# sensors.net
KiCad netlist of a schematic drawn in Altium Designer
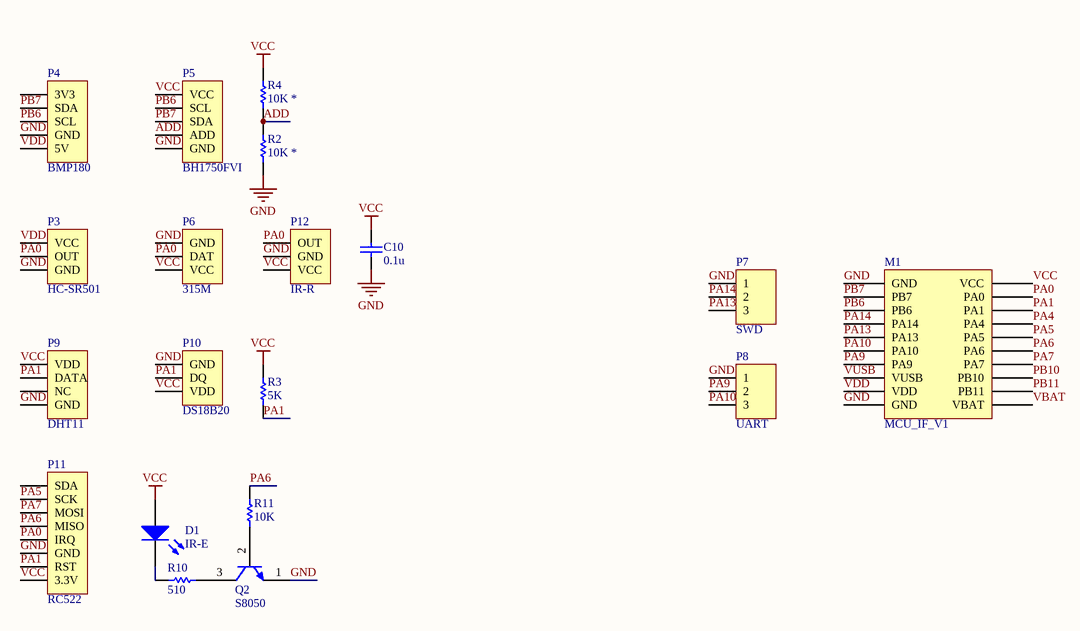
[diagram p0: sensors.SchDoc]

(export (version "E")
  (design (tool "Eeschema 10.0.6"))
  (components
    (comp (ref "C10")
      (value "0.1u")
      (footprint "C-1608[0603]")
      (description "Capacitor (Semiconductor SIM Model)")
      (fields (field (name "Comment") "Cap Semi") (field (name "PUBLISHER") "Altium Limited"))
      (libsource (lib "Miscellaneous Devices") (part "Cap Semi"))
    )
    (comp (ref "D1")
      (value "IR-E")
      (footprint "PIN2")
      (description "Typical INFRARED GaAs LED")
      (fields (field (name "PUBLISHER") "Altium Limited"))
      (libsource (lib "Miscellaneous Devices") (part "LED0"))
    )
    (comp (ref "M1")
      (value "MCU_IF_V1")
      (footprint "MCU_IF_V1")
      (libsource (lib "MCU_IF") (part "MCU_IF_V1"))
    )
    (comp (ref "P3")
      (value "HC-SR501")
      (footprint "HDR1X3")
      (description "Header, 3-Pin")
      (fields (field (name "PUBLISHER") "Altium Limited"))
      (libsource (lib "sensor_ifce") (part "HC-SR501"))
    )
    (comp (ref "P4")
      (value "BMP180")
      (footprint "HDR1X5")
      (description "Header, 5-Pin")
      (fields (field (name "PUBLISHER") "Altium Limited"))
      (libsource (lib "sensor_ifce") (part "BMP180"))
    )
    (comp (ref "P5")
      (value "BH1750FVI")
      (footprint "HDR1X5")
      (fields (field (name "PUBLISHER") "Altium Limited"))
      (libsource (lib "sensor_ifce") (part "BH1750FVI"))
    )
    (comp (ref "P6")
      (value "315M")
      (footprint "HDR1X3")
      (description "Header, 3-Pin")
      (fields (field (name "PUBLISHER") "Altium Limited"))
      (libsource (lib "sensor_ifce") (part "315M"))
    )
    (comp (ref "P7")
      (value "SWD")
      (footprint "HDR1X3")
      (description "Header, 3-Pin")
      (fields (field (name "PUBLISHER") "Altium Limited"))
      (libsource (lib "Miscellaneous Connectors") (part "Header 3"))
    )
    (comp (ref "P8")
      (value "UART")
      (footprint "HDR1X3")
      (description "Header, 3-Pin")
      (fields (field (name "PUBLISHER") "Altium Limited"))
      (libsource (lib "Miscellaneous Connectors") (part "Header 3"))
    )
    (comp (ref "P9")
      (value "DHT11")
      (footprint "HDR1X4")
      (description "Header, 4-Pin")
      (fields (field (name "PUBLISHER") "Altium Limited"))
      (libsource (lib "sensor_ifce") (part "DHT11"))
    )
    (comp (ref "P10")
      (value "DS18B20")
      (footprint "HDR1X3")
      (description "Header, 3-Pin")
      (fields (field (name "PUBLISHER") "Altium Limited"))
      (libsource (lib "sensor_ifce") (part "DS18B20"))
    )
    (comp (ref "P11")
      (value "RC522")
      (footprint "HDR1X8")
      (description "Header, 8-Pin")
      (fields (field (name "PUBLISHER") "Altium Limited"))
      (libsource (lib "sensor_ifce") (part "RC522"))
    )
    (comp (ref "P12")
      (value "IR-R")
      (footprint "HDR1X3")
      (description "Header, 3-Pin")
      (fields (field (name "PUBLISHER") "Altium Limited"))
      (libsource (lib "sensor_ifce") (part "IR"))
    )
    (comp (ref "Q2")
      (value "S8050")
      (footprint "SOT23B")
      (description "NPN General Purpose Amplifier")
      (fields (field (name "PUBLISHER") "Altium Limited"))
      (libsource (lib "Miscellaneous Devices") (part "2N3904"))
    )
    (comp (ref "R2")
      (value "10K *")
      (footprint "R-1608[0603]")
      (description "Semiconductor Resistor")
      (fields (field (name "Comment") "Res Semi") (field (name "PUBLISHER") "Altium Limited"))
      (libsource (lib "Miscellaneous Devices") (part "Res Semi"))
    )
    (comp (ref "R3")
      (value "5K")
      (footprint "R-1608[0603]")
      (description "Semiconductor Resistor")
      (fields (field (name "Comment") "Res Semi") (field (name "PUBLISHER") "Altium Limited"))
      (libsource (lib "Miscellaneous Devices") (part "Res Semi"))
    )
    (comp (ref "R4")
      (value "10K *")
      (footprint "R-1608[0603]")
      (description "Semiconductor Resistor")
      (fields (field (name "Comment") "Res Semi") (field (name "PUBLISHER") "Altium Limited"))
      (libsource (lib "Miscellaneous Devices") (part "Res Semi"))
    )
    (comp (ref "R10")
      (value "510")
      (footprint "R-1608[0603]")
      (description "Semiconductor Resistor")
      (fields (field (name "Comment") "Res Semi") (field (name "PUBLISHER") "Altium Limited"))
      (libsource (lib "Miscellaneous Devices") (part "Res Semi"))
    )
    (comp (ref "R11")
      (value "10K")
      (footprint "R-1608[0603]")
      (description "Semiconductor Resistor")
      (fields (field (name "Comment") "Res Semi") (field (name "PUBLISHER") "Altium Limited"))
      (libsource (lib "Miscellaneous Devices") (part "Res Semi"))
    )
  )
  (nets
    (net (code "1") (name "/ADD") (class "Default")
      (node (ref "P5") (pin "4") (pinfunction "ADD_4") (pintype "passive"))
      (node (ref "R2") (pin "1") (pinfunction "1_1") (pintype "passive"))
      (node (ref "R4") (pin "2") (pinfunction "2_2") (pintype "passive"))
    )
    (net (code "2") (name "/PA0") (class "Default")
      (node (ref "M1") (pin "19") (pinfunction "PA0_19") (pintype "passive"))
      (node (ref "P11") (pin "5") (pinfunction "IRQ_5") (pintype "passive"))
      (node (ref "P12") (pin "1") (pinfunction "OUT_1") (pintype "passive"))
      (node (ref "P3") (pin "2") (pinfunction "OUT_2") (pintype "passive"))
      (node (ref "P6") (pin "2") (pinfunction "DAT_2") (pintype "passive"))
    )
    (net (code "3") (name "/PA1") (class "Default")
      (node (ref "M1") (pin "18") (pinfunction "PA1_18") (pintype "passive"))
      (node (ref "P10") (pin "2") (pinfunction "DQ_2") (pintype "passive"))
      (node (ref "P11") (pin "7") (pinfunction "RST_7") (pintype "passive"))
      (node (ref "P9") (pin "2") (pinfunction "DATA_2") (pintype "passive"))
      (node (ref "R3") (pin "2") (pinfunction "2_2") (pintype "passive"))
    )
    (net (code "4") (name "/PA4") (class "Default")
      (node (ref "M1") (pin "17") (pinfunction "PA4_17") (pintype "passive"))
    )
    (net (code "5") (name "/PA5") (class "Default")
      (node (ref "M1") (pin "16") (pinfunction "PA5_16") (pintype "passive"))
      (node (ref "P11") (pin "2") (pinfunction "SCK_2") (pintype "passive"))
    )
    (net (code "6") (name "/PA6") (class "Default")
      (node (ref "M1") (pin "15") (pinfunction "PA6_15") (pintype "passive"))
      (node (ref "P11") (pin "4") (pinfunction "MISO_4") (pintype "passive"))
      (node (ref "R11") (pin "2") (pinfunction "2_2") (pintype "passive"))
    )
    (net (code "7") (name "/PA7") (class "Default")
      (node (ref "M1") (pin "14") (pinfunction "PA7_14") (pintype "passive"))
      (node (ref "P11") (pin "3") (pinfunction "MOSI_3") (pintype "passive"))
    )
    (net (code "8") (name "/PA9") (class "Default")
      (node (ref "M1") (pin "7") (pinfunction "PA9_7") (pintype "passive"))
      (node (ref "P8") (pin "2") (pinfunction "2_2") (pintype "passive"))
    )
    (net (code "9") (name "/PA10") (class "Default")
      (node (ref "M1") (pin "6") (pinfunction "PA10_6") (pintype "passive"))
      (node (ref "P8") (pin "3") (pinfunction "3_3") (pintype "passive"))
    )
    (net (code "10") (name "/PA13") (class "Default")
      (node (ref "M1") (pin "5") (pinfunction "PA13_5") (pintype "passive"))
      (node (ref "P7") (pin "3") (pinfunction "3_3") (pintype "passive"))
    )
    (net (code "11") (name "/PA14") (class "Default")
      (node (ref "M1") (pin "4") (pinfunction "PA14_4") (pintype "passive"))
      (node (ref "P7") (pin "2") (pinfunction "2_2") (pintype "passive"))
    )
    (net (code "12") (name "/PB6") (class "Default")
      (node (ref "M1") (pin "3") (pinfunction "PB6_3") (pintype "passive"))
      (node (ref "P4") (pin "3") (pinfunction "SCL_3") (pintype "passive"))
      (node (ref "P5") (pin "2") (pinfunction "SCL_2") (pintype "passive"))
    )
    (net (code "13") (name "/PB7") (class "Default")
      (node (ref "M1") (pin "2") (pinfunction "PB7_2") (pintype "passive"))
      (node (ref "P4") (pin "2") (pinfunction "SDA_2") (pintype "passive"))
      (node (ref "P5") (pin "3") (pinfunction "SDA_3") (pintype "passive"))
    )
    (net (code "14") (name "/PB10") (class "Default")
      (node (ref "M1") (pin "13") (pinfunction "PB10_13") (pintype "passive"))
    )
    (net (code "15") (name "/PB11") (class "Default")
      (node (ref "M1") (pin "12") (pinfunction "PB11_12") (pintype "passive"))
    )
    (net (code "16") (name "/VBAT") (class "Default")
      (node (ref "M1") (pin "11") (pinfunction "VBAT_11") (pintype "passive"))
    )
    (net (code "17") (name "/VDD") (class "Default")
      (node (ref "M1") (pin "9") (pinfunction "VDD_9") (pintype "passive"))
      (node (ref "P3") (pin "1") (pinfunction "VCC_1") (pintype "passive"))
      (node (ref "P4") (pin "5") (pinfunction "5V_5") (pintype "passive"))
    )
    (net (code "18") (name "/VUSB") (class "Default")
      (node (ref "M1") (pin "8") (pinfunction "VUSB_8") (pintype "passive"))
    )
    (net (code "19") (name "GND") (class "Default")
      (node (ref "C10") (pin "1") (pinfunction "1_1") (pintype "passive"))
      (node (ref "M1") (pin "1") (pinfunction "GND_1") (pintype "passive"))
      (node (ref "M1") (pin "10") (pinfunction "GND_10") (pintype "passive"))
      (node (ref "P10") (pin "1") (pinfunction "GND_1") (pintype "passive"))
      (node (ref "P11") (pin "6") (pinfunction "GND_6") (pintype "passive"))
      (node (ref "P12") (pin "2") (pinfunction "GND_2") (pintype "passive"))
      (node (ref "P3") (pin "3") (pinfunction "GND_3") (pintype "passive"))
      (node (ref "P4") (pin "4") (pinfunction "GND_4") (pintype "passive"))
      (node (ref "P5") (pin "5") (pinfunction "GND_5") (pintype "passive"))
      (node (ref "P6") (pin "1") (pinfunction "GND_1") (pintype "passive"))
      (node (ref "P7") (pin "1") (pinfunction "1_1") (pintype "passive"))
      (node (ref "P8") (pin "1") (pinfunction "1_1") (pintype "passive"))
      (node (ref "P9") (pin "4") (pinfunction "GND_4") (pintype "passive"))
      (node (ref "Q2") (pin "1") (pinfunction "E_1") (pintype "passive"))
      (node (ref "R2") (pin "2") (pinfunction "2_2") (pintype "passive"))
    )
    (net (code "20") (name "Net-(D1-K)") (class "Default")
      (node (ref "D1") (pin "2") (pinfunction "K_2") (pintype "passive"))
      (node (ref "R10") (pin "1") (pinfunction "1_1") (pintype "passive"))
    )
    (net (code "21") (name "Net-(Q2-B)") (class "Default")
      (node (ref "Q2") (pin "2") (pinfunction "B_2") (pintype "passive"))
      (node (ref "R11") (pin "1") (pinfunction "1_1") (pintype "passive"))
    )
    (net (code "22") (name "Net-(Q2-C)") (class "Default")
      (node (ref "Q2") (pin "3") (pinfunction "C_3") (pintype "passive"))
      (node (ref "R10") (pin "2") (pinfunction "2_2") (pintype "passive"))
    )
    (net (code "23") (name "VCC") (class "Default")
      (node (ref "C10") (pin "2") (pinfunction "2_2") (pintype "passive"))
      (node (ref "D1") (pin "1") (pinfunction "A_1") (pintype "passive"))
      (node (ref "M1") (pin "20") (pinfunction "VCC_20") (pintype "passive"))
      (node (ref "P10") (pin "3") (pinfunction "VDD_3") (pintype "passive"))
      (node (ref "P11") (pin "8") (pinfunction "3.3V_8") (pintype "passive"))
      (node (ref "P12") (pin "3") (pinfunction "VCC_3") (pintype "passive"))
      (node (ref "P5") (pin "1") (pinfunction "VCC_1") (pintype "passive"))
      (node (ref "P6") (pin "3") (pinfunction "VCC_3") (pintype "passive"))
      (node (ref "P9") (pin "1") (pinfunction "VDD_1") (pintype "passive"))
      (node (ref "R3") (pin "1") (pinfunction "1_1") (pintype "passive"))
      (node (ref "R4") (pin "1") (pinfunction "1_1") (pintype "passive"))
    )
    (net (code "24") (name "unconnected-(P4-3V3-Pad1)") (class "Default")
      (node (ref "P4") (pin "1") (pinfunction "3V3_1") (pintype "passive"))
    )
    (net (code "25") (name "unconnected-(P9-NC-Pad3)") (class "Default")
      (node (ref "P9") (pin "3") (pinfunction "NC_3") (pintype "passive"))
    )
    (net (code "26") (name "unconnected-(P11-SDA-Pad1)") (class "Default")
      (node (ref "P11") (pin "1") (pinfunction "SDA_1") (pintype "passive"))
    )
  )
)
